# POWER.net
KiCad netlist of a schematic drawn in Altium Designer
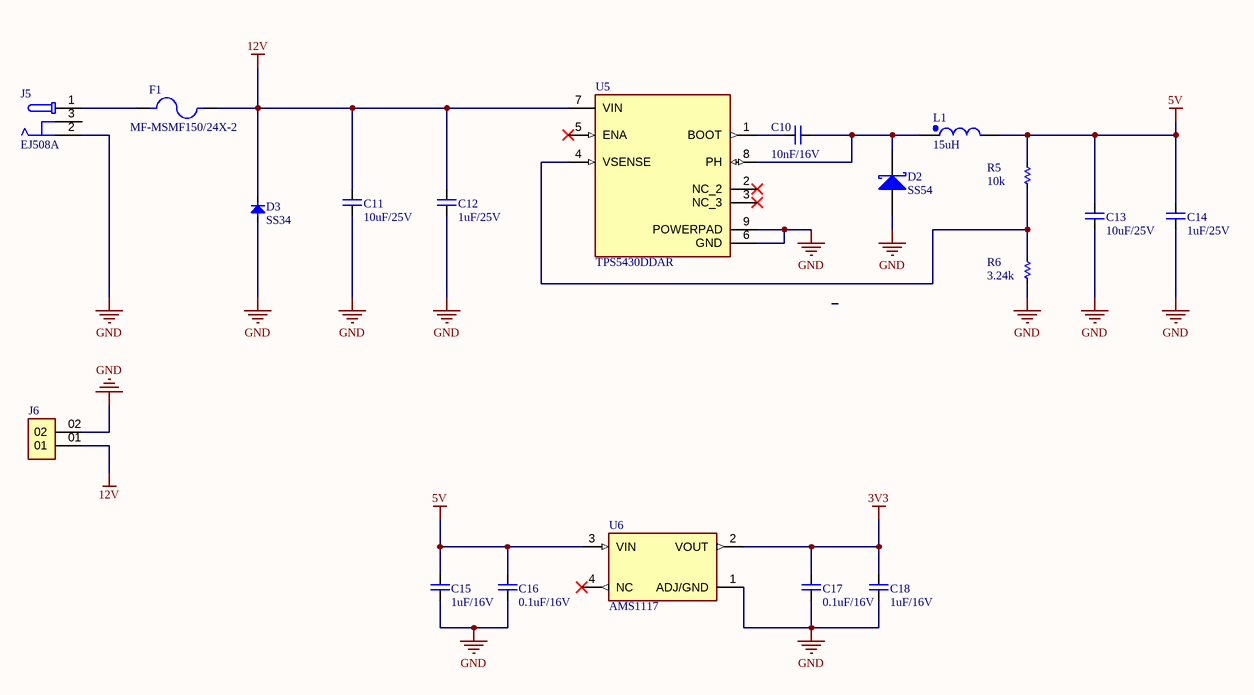
[diagram p0: POWER.SchDoc]

(export (version "E")
  (design (tool "Eeschema 10.0.6"))
  (components
    (comp (ref "C10")
      (value "10nF/16V")
      (footprint "CAP_C_1608X80")
      (description "CAP_Chip")
      (libsource (lib "LABLIB") (part "CAP_SMD"))
    )
    (comp (ref "C11")
      (value "10uF/25V")
      (footprint "CAP_C_1608X80")
      (description "CAP_Chip")
      (libsource (lib "LABLIB") (part "CAP_SMD"))
    )
    (comp (ref "C12")
      (value "1uF/25V")
      (footprint "CAP_C_1608X80")
      (description "CAP_Chip")
      (libsource (lib "LABLIB") (part "CAP_SMD"))
    )
    (comp (ref "C13")
      (value "10uF/25V")
      (footprint "CAP_C_1608X80")
      (description "CAP_Chip")
      (libsource (lib "LABLIB") (part "CAP_SMD"))
    )
    (comp (ref "C14")
      (value "1uF/25V")
      (footprint "CAP_C_1608X80")
      (description "CAP_Chip")
      (libsource (lib "LABLIB") (part "CAP_SMD"))
    )
    (comp (ref "C15")
      (value "1uF/16V")
      (footprint "CAP_C_1608X80")
      (description "CAP_Chip")
      (libsource (lib "BTL_SCHLIB") (part "CAP_SMD"))
    )
    (comp (ref "C16")
      (value "0.1uF/16V")
      (footprint "CAP_C_1608X80")
      (description "CAP_Chip")
      (libsource (lib "BTL_SCHLIB") (part "CAP_SMD"))
    )
    (comp (ref "C17")
      (value "0.1uF/16V")
      (footprint "CAP_C_1608X80")
      (description "CAP_Chip")
      (libsource (lib "BTL_SCHLIB") (part "CAP_SMD"))
    )
    (comp (ref "C18")
      (value "1uF/16V")
      (footprint "CAP_C_1608X80")
      (description "CAP_Chip")
      (libsource (lib "BTL_SCHLIB") (part "CAP_SMD"))
    )
    (comp (ref "D2")
      (value "SS54")
      (footprint "DO-214AC_SMA")
      (description "DIODE SCHOTTKY 40V 5A SMA")
      (fields (field (name "MPN") "SS34"))
      (libsource (lib "COMM_SCHLIB") (part "SS54"))
    )
    (comp (ref "D3")
      (value "SS34")
      (footprint "DO-214AC_SMA")
      (description "Default Diode")
      (fields (field (name "PUBLISHER") "Altium Limited"))
      (libsource (lib "BTL_SCHLIB") (part "Diode SMD"))
    )
    (comp (ref "F1")
      (value "MF-MSMF150/24X-2")
      (footprint "FUSER_MF-MSMF150/24X-2")
      (description "Polymeric PTC Resettable Fuse 24V 1.5 A Ih Surface Mount 1812 (4532 Metric), Concave")
      (fields (field (name "DIGI-KEY_PART_NUMBER") "MF-MSMF150/24X-2TR-ND") (field (name "MF") "Bourns"))
      (libsource (lib "BTL_SCHLIB") (part "MF-MSMF150/24X-2"))
    )
    (comp (ref "J5")
      (value "EJ508A")
      (footprint "MPD_EJ508A")
      (description "Power Barrel Connector Jack 2.10mm ID _0.083_, 5.50mm OD _0.217_ Through Hole, Right Angle")
      (fields (field (name "MF") "MPD"))
      (libsource (lib "BTL_SCHLIB") (part "EJ508A"))
    )
    (comp (ref "J6")
      (value "MTSW-102-08-G-S-100-RA")
      (footprint "SAMTEC_MTSW-102-08-G-S-100-RA")
      (description "Connector Header Through Hole, Right Angle 2 position 0.100 (2.54mm)")
      (fields (field (name "MF") "Samtec"))
      (libsource (lib "BTL_SCHLIB") (part "MTSW-102-08-G-S-100-RA"))
    )
    (comp (ref "L1")
      (value "15uH")
      (footprint "IND_CDRH127/LDNP-470MC_SUM")
      (libsource (lib "BTL_SCHLIB") (part "_IND"))
    )
    (comp (ref "R5")
      (value "10k")
      (footprint "RES_C_1608X60")
      (description "RES")
      (libsource (lib "LABLIB") (part "_RES_B_2"))
    )
    (comp (ref "R6")
      (value "3.24k")
      (footprint "RES_C_1608X60")
      (description "RES")
      (libsource (lib "LABLIB") (part "_RES_B_2"))
    )
    (comp (ref "U5")
      (value "TPS5430DDAR")
      (footprint "CONV_TPS5430DDAR")
      (description "5.5V to 36V Input, 3A, 500kHz Step-Down Converter")
      (fields (field (name "MF") "Texas Instruments"))
      (libsource (lib "BTL_SCHLIB") (part "TPS5430DDAR"))
    )
    (comp (ref "U6")
      (value "AMS1117")
      (footprint "SOT229P700X180-4N")
      (description "1A LOW DROPOUT VOLTAGE REGULATOR SOT-223")
      (fields (field (name "MF") "Advanced Monolithic Systems"))
      (libsource (lib "BTL_SCHLIB") (part "AMS1117"))
    )
  )
  (nets
    (net (code "1") (name "3V3") (class "Default")
      (node (ref "C17") (pin "2") (pinfunction "2_2") (pintype "passive"))
      (node (ref "C18") (pin "2") (pinfunction "2_2") (pintype "passive"))
      (node (ref "U6") (pin "2") (pinfunction "VOUT_2") (pintype "output"))
    )
    (net (code "2") (name "5V") (class "Default")
      (node (ref "C13") (pin "2") (pinfunction "2_2") (pintype "passive"))
      (node (ref "C14") (pin "2") (pinfunction "2_2") (pintype "passive"))
      (node (ref "C15") (pin "2") (pinfunction "2_2") (pintype "passive"))
      (node (ref "C16") (pin "2") (pinfunction "2_2") (pintype "passive"))
      (node (ref "L1") (pin "2") (pinfunction "2_2") (pintype "passive"))
      (node (ref "R5") (pin "1") (pinfunction "1_1") (pintype "passive"))
      (node (ref "U6") (pin "3") (pinfunction "VIN_3") (pintype "input"))
    )
    (net (code "3") (name "12V") (class "Default")
      (node (ref "C11") (pin "2") (pinfunction "2_2") (pintype "passive"))
      (node (ref "C12") (pin "2") (pinfunction "2_2") (pintype "passive"))
      (node (ref "D3") (pin "1") (pinfunction "K_1") (pintype "passive"))
      (node (ref "F1") (pin "2") (pinfunction "2_2") (pintype "passive"))
      (node (ref "J6") (pin "01") (pinfunction "01_01") (pintype "passive"))
      (node (ref "U5") (pin "7") (pinfunction "VIN_7") (pintype "power_in"))
    )
    (net (code "4") (name "GND") (class "Default")
      (node (ref "C11") (pin "1") (pinfunction "1_1") (pintype "passive"))
      (node (ref "C12") (pin "1") (pinfunction "1_1") (pintype "passive"))
      (node (ref "C13") (pin "1") (pinfunction "1_1") (pintype "passive"))
      (node (ref "C14") (pin "1") (pinfunction "1_1") (pintype "passive"))
      (node (ref "C15") (pin "1") (pinfunction "1_1") (pintype "passive"))
      (node (ref "C16") (pin "1") (pinfunction "1_1") (pintype "passive"))
      (node (ref "C17") (pin "1") (pinfunction "1_1") (pintype "passive"))
      (node (ref "C18") (pin "1") (pinfunction "1_1") (pintype "passive"))
      (node (ref "D2") (pin "1") (pinfunction "A_1") (pintype "passive"))
      (node (ref "D3") (pin "2") (pinfunction "A_2") (pintype "passive"))
      (node (ref "J5") (pin "2") (pinfunction "2_2") (pintype "passive"))
      (node (ref "J6") (pin "02") (pinfunction "02_02") (pintype "passive"))
      (node (ref "R6") (pin "2") (pinfunction "2_2") (pintype "passive"))
      (node (ref "U5") (pin "6") (pinfunction "GND_6") (pintype "power_in"))
      (node (ref "U5") (pin "9") (pinfunction "POWERPAD_9") (pintype "power_in"))
      (node (ref "U6") (pin "1") (pinfunction "ADJ/GND_1") (pintype "power_in"))
    )
    (net (code "5") (name "Net-(D2-K)") (class "Default")
      (node (ref "C10") (pin "1") (pinfunction "1_1") (pintype "passive"))
      (node (ref "D2") (pin "2") (pinfunction "K_2") (pintype "passive"))
      (node (ref "L1") (pin "1") (pinfunction "1_1") (pintype "passive"))
      (node (ref "U5") (pin "8") (pinfunction "PH_8") (pintype "bidirectional"))
    )
    (net (code "6") (name "Net-(F1-Pad1)") (class "Default")
      (node (ref "F1") (pin "1") (pinfunction "1_1") (pintype "passive"))
      (node (ref "J5") (pin "1") (pinfunction "1_1") (pintype "passive"))
    )
    (net (code "7") (name "Net-(U5-BOOT)") (class "Default")
      (node (ref "C10") (pin "2") (pinfunction "2_2") (pintype "passive"))
      (node (ref "U5") (pin "1") (pinfunction "BOOT_1") (pintype "output"))
    )
    (net (code "8") (name "Net-(U5-VSENSE)") (class "Default")
      (node (ref "R5") (pin "2") (pinfunction "2_2") (pintype "passive"))
      (node (ref "R6") (pin "1") (pinfunction "1_1") (pintype "passive"))
      (node (ref "U5") (pin "4") (pinfunction "VSENSE_4") (pintype "input"))
    )
    (net (code "9") (name "unconnected-(J5-Pad3)") (class "Default")
      (node (ref "J5") (pin "3") (pinfunction "3_3") (pintype "passive"))
    )
    (net (code "10") (name "unconnected-(U5-ENA-Pad5)") (class "Default")
      (node (ref "U5") (pin "5") (pinfunction "ENA_5") (pintype "input+no_connect"))
    )
    (net (code "11") (name "unconnected-(U5-NC_2-Pad2)") (class "Default")
      (node (ref "U5") (pin "2") (pinfunction "NC_2_2") (pintype "passive+no_connect"))
    )
    (net (code "12") (name "unconnected-(U5-NC_3-Pad3)") (class "Default")
      (node (ref "U5") (pin "3") (pinfunction "NC_3_3") (pintype "passive+no_connect"))
    )
    (net (code "13") (name "unconnected-(U6-NC-Pad4)") (class "Default")
      (node (ref "U6") (pin "4") (pinfunction "NC_4") (pintype "output+no_connect"))
    )
  )
)
